# SmartHive_Client.net
KiCad netlist of a schematic drawn in Altium Designer
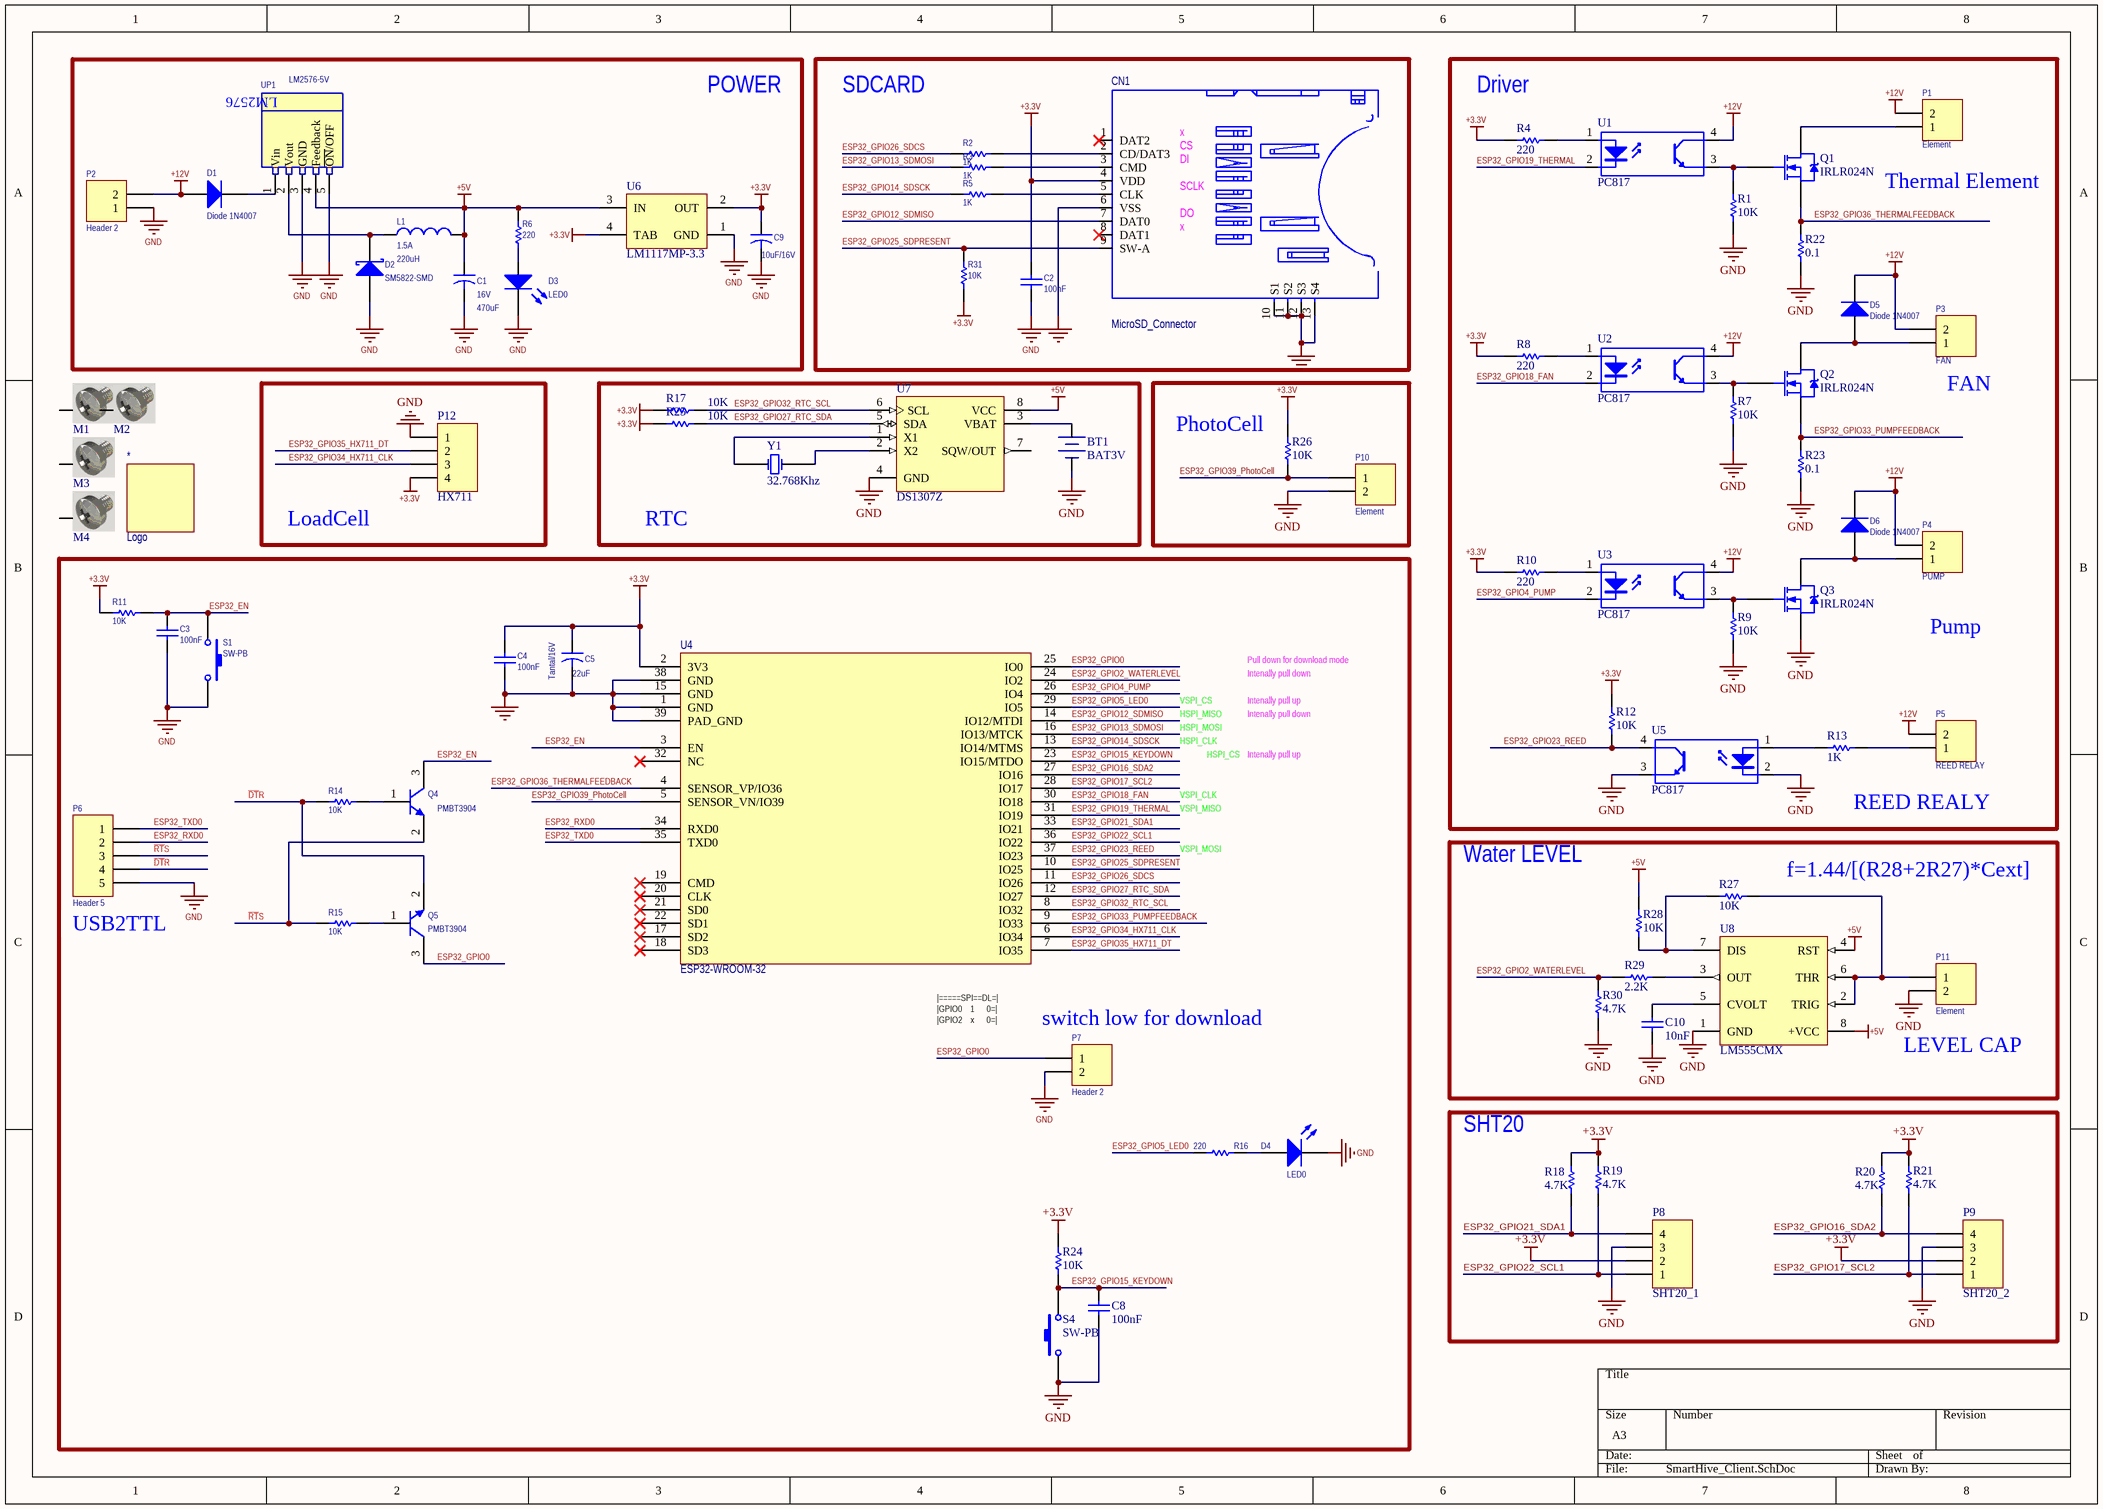
[diagram p0: SmartHive_Client.SchDoc]

(export (version "E")
  (design (tool "Eeschema 10.0.6"))
  (components
    (comp (ref "*") (value "Logo") (footprint "LOGO_PARS_TOP") (libsource (lib "Mofidi3D") (part "Logo")))
    (comp (ref "BT1")
      (value "BAT3V")
      (footprint "BTH2032_DIP")
      (description "Battry Backup")
      (fields (field (name "DESIGNER") "Abbas Basereh"))
      (libsource (lib "Mofidi3D") (part "Battry Backup"))
    )
    (comp (ref "C1")
      (value "16V")
      (footprint "Cap electrolitic radial 8x12-3.5")
      (description "Capacitor")
      (fields (field (name "ALTIUM_VALUE") "470uF") (field (name "PUBLISHER") "Altium Limited"))
      (libsource (lib "Miscellaneous Devices") (part "Cap2"))
    )
    (comp (ref "C2")
      (value "100nF")
      (footprint "CAP0805")
      (description "Capacitor")
      (fields (field (name "PUBLISHER") "Altium Limited"))
      (libsource (lib "Miscellaneous Devices") (part "Cap"))
    )
    (comp (ref "C3")
      (value "100nF")
      (footprint "CAP0805")
      (description "Capacitor")
      (fields (field (name "PUBLISHER") "Altium Limited"))
      (libsource (lib "Miscellaneous Devices") (part "Cap"))
    )
    (comp (ref "C4")
      (value "100nF")
      (footprint "CAP0805")
      (description "Capacitor")
      (fields (field (name "PUBLISHER") "Altium Limited"))
      (libsource (lib "Miscellaneous Devices") (part "Cap"))
    )
    (comp (ref "C5")
      (value "Tantal/16V")
      (footprint "CAP_TANTAL_TYPE_B")
      (description "Capacitor")
      (fields (field (name "ALTIUM_VALUE") "22uF") (field (name "PUBLISHER") "Altium Limited"))
      (libsource (lib "Miscellaneous Devices") (part "Cap2"))
    )
    (comp (ref "C8")
      (value "100nF")
      (footprint "CAP0805")
      (description "Capacitor")
      (fields (field (name "PUBLISHER") "Altium Limited"))
      (libsource (lib "Miscellaneous Devices") (part "Cap"))
    )
    (comp (ref "C9")
      (value "10uF/16V")
      (footprint "Cap electrolitic radial 5x11-2")
      (description "Capacitor")
      (fields (field (name "PUBLISHER") "Altium Limited"))
      (libsource (lib "Miscellaneous Devices") (part "Cap2"))
    )
    (comp (ref "C10")
      (value "10nF")
      (footprint "CAP0805")
      (description "Capacitor")
      (fields (field (name "PUBLISHER") "Altium Limited"))
      (libsource (lib "Miscellaneous Devices") (part "Cap"))
    )
    (comp (ref "CN1")
      (value "MicroSD_Connector")
      (footprint "MICRO_SD_TFP-09-2-12B")
      (libsource (lib "Mofidi3D") (part "MicroSD_Connector"))
    )
    (comp (ref "D1")
      (value "Diode 1N4007")
      (footprint "DO-241AC")
      (description "1 Amp General Purpose Rectifier")
      (fields (field (name "PUBLISHER") "Altium Limited"))
      (libsource (lib "Miscellaneous Devices") (part "Diode 1N4007"))
    )
    (comp (ref "D2")
      (value "SM5822-SMD")
      (footprint "430X270D")
      (description "Schottky Diode")
      (fields (field (name "PUBLISHER") "Altium Limited"))
      (libsource (lib "Miscellaneous Devices") (part "D Schottky"))
    )
    (comp (ref "D3")
      (value "LED0")
      (footprint "LED5MM_GRN")
      (description "Typical INFRARED GaAs LED")
      (fields (field (name "PUBLISHER") "Altium Limited"))
      (libsource (lib "Miscellaneous Devices") (part "LED0"))
    )
    (comp (ref "D4")
      (value "LED0")
      (footprint "LED5MM_BLUE")
      (description "Typical INFRARED GaAs LED")
      (fields (field (name "PUBLISHER") "Altium Limited"))
      (libsource (lib "Miscellaneous Devices") (part "LED0"))
    )
    (comp (ref "D5")
      (value "Diode 1N4007")
      (footprint "DO-241AC")
      (description "1 Amp General Purpose Rectifier")
      (fields (field (name "PUBLISHER") "Altium Limited"))
      (libsource (lib "Miscellaneous Devices") (part "Diode 1N4007"))
    )
    (comp (ref "D6")
      (value "Diode 1N4007")
      (footprint "DO-241AC")
      (description "1 Amp General Purpose Rectifier")
      (fields (field (name "PUBLISHER") "Altium Limited"))
      (libsource (lib "Miscellaneous Devices") (part "Diode 1N4007"))
    )
    (comp (ref "L1")
      (value "1.5A")
      (footprint "Inductor 10x12 (200 mils)")
      (description "Inductor")
      (fields (field (name "ALTIUM_VALUE") "220uH") (field (name "PUBLISHER") "Altium Limited"))
      (libsource (lib "Miscellaneous Devices") (part "Inductor"))
    )
    (comp (ref "M1")
      (value "Screw3mm")
      (footprint "Board Screw 3mm")
      (description "Board Screw With Spacer 3mm")
      (fields (field (name "DESIGNER") "Abbas Basereh"))
      (libsource (lib "Mofidi3D") (part "Board Screw 3mm"))
    )
    (comp (ref "M2")
      (value "Screw3mm")
      (footprint "Board Screw 3mm")
      (description "Board Screw With Spacer 3mm")
      (fields (field (name "DESIGNER") "Abbas Basereh"))
      (libsource (lib "Mofidi3D") (part "Board Screw 3mm"))
    )
    (comp (ref "M3")
      (value "Screw3mm")
      (footprint "Board Screw 3mm")
      (description "Board Screw With Spacer 3mm")
      (fields (field (name "DESIGNER") "Abbas Basereh"))
      (libsource (lib "Mofidi3D") (part "Board Screw 3mm"))
    )
    (comp (ref "M4")
      (value "Screw3mm")
      (footprint "Board Screw 3mm")
      (description "Board Screw With Spacer 3mm")
      (fields (field (name "DESIGNER") "Abbas Basereh"))
      (libsource (lib "Mofidi3D") (part "Board Screw 3mm"))
    )
    (comp (ref "P1")
      (value "Element")
      (footprint "MSTBV 2,5/2-G-5")
      (description "Header, 2-Pin")
      (fields (field (name "PUBLISHER") "Altium Limited"))
      (libsource (lib "Miscellaneous Connectors") (part "Header 2"))
    )
    (comp (ref "P2")
      (value "Header 2")
      (footprint "MSTBV 2,5/2-G-5")
      (description "Header, 2-Pin")
      (fields (field (name "PUBLISHER") "Altium Limited"))
      (libsource (lib "") (part "Header 2_2"))
    )
    (comp (ref "P3")
      (value "FAN")
      (footprint "MSTBV 2,5/2-G-5")
      (description "Header, 2-Pin")
      (fields (field (name "PUBLISHER") "Altium Limited"))
      (libsource (lib "Miscellaneous Connectors") (part "Header 2"))
    )
    (comp (ref "P4")
      (value "PUMP")
      (footprint "MSTBV 2,5/2-G-5")
      (description "Header, 2-Pin")
      (fields (field (name "PUBLISHER") "Altium Limited"))
      (libsource (lib "Miscellaneous Connectors") (part "Header 2"))
    )
    (comp (ref "P5")
      (value "REED RELAY")
      (footprint "MSTBV 2,5/2-G-5")
      (description "Header, 2-Pin")
      (fields (field (name "PUBLISHER") "Altium Limited"))
      (libsource (lib "Miscellaneous Connectors") (part "Header 2"))
    )
    (comp (ref "P6")
      (value "Header 5")
      (footprint "HDR1X5")
      (description "Header, 5-Pin")
      (fields (field (name "PUBLISHER") "Altium Limited"))
      (libsource (lib "Miscellaneous Connectors") (part "Header 5"))
    )
    (comp (ref "P7")
      (value "Header 2")
      (footprint "Jumper Small - 2.54 - Black")
      (description "Header, 2-Pin")
      (fields (field (name "PUBLISHER") "Altium Limited"))
      (libsource (lib "") (part "Header 2_1"))
    )
    (comp (ref "P8")
      (value "SHT20_1")
      (footprint "XH-4PIN")
      (description "Header, 4-Pin")
      (fields (field (name "PUBLISHER") "Altium Limited"))
      (libsource (lib "Miscellaneous Connectors") (part "Header 4"))
    )
    (comp (ref "P9")
      (value "SHT20_2")
      (footprint "XH-4PIN")
      (description "Header, 4-Pin")
      (fields (field (name "PUBLISHER") "Altium Limited"))
      (libsource (lib "Miscellaneous Connectors") (part "Header 4"))
    )
    (comp (ref "P10")
      (value "Element")
      (footprint "DS1070-2-COMCON")
      (description "Header, 2-Pin")
      (fields (field (name "PUBLISHER") "Altium Limited"))
      (libsource (lib "") (part "Header 2_1"))
    )
    (comp (ref "P11")
      (value "Element")
      (footprint "DS1070-2-COMCON")
      (description "Header, 2-Pin")
      (fields (field (name "PUBLISHER") "Altium Limited"))
      (libsource (lib "") (part "Header 2_1"))
    )
    (comp (ref "P12")
      (value "HX711")
      (footprint "HDR1X4")
      (description "Header, 4-Pin")
      (fields (field (name "PUBLISHER") "Altium Limited"))
      (libsource (lib "") (part "Header 4_1"))
    )
    (comp (ref "Q1")
      (value "IRLR024N")
      (footprint "TO252-3M")
      (description "HEXFET Power MOSFET")
      (fields (field (name "PUBLISHER") "Altium Limited"))
      (libsource (lib "IR Discrete MOSFET - Power") (part "IRLR024N"))
    )
    (comp (ref "Q2")
      (value "IRLR024N")
      (footprint "TO252-3M")
      (description "HEXFET Power MOSFET")
      (fields (field (name "PUBLISHER") "Altium Limited"))
      (libsource (lib "IR Discrete MOSFET - Power") (part "IRLR024N"))
    )
    (comp (ref "Q3")
      (value "IRLR024N")
      (footprint "TO252-3M")
      (description "HEXFET Power MOSFET")
      (fields (field (name "PUBLISHER") "Altium Limited"))
      (libsource (lib "IR Discrete MOSFET - Power") (part "IRLR024N"))
    )
    (comp (ref "Q4")
      (value "PMBT3904")
      (footprint "Mofidi3D:SOT23_M")
      (description "NPN Switching Transistor")
      (fields (field (name "PUBLISHER") "Altium Limited"))
      (libsource (lib "Philips Discrete BJT - Low Power") (part "PMBT3904"))
    )
    (comp (ref "Q5")
      (value "PMBT3904")
      (footprint "Mofidi3D:SOT23_M")
      (description "NPN Switching Transistor")
      (fields (field (name "PUBLISHER") "Altium Limited"))
      (libsource (lib "Philips Discrete BJT - Low Power") (part "PMBT3904"))
    )
    (comp (ref "R1")
      (value "10K")
      (footprint "RES0805")
      (description "Resistor")
      (fields (field (name "PUBLISHER") "Altium Limited"))
      (libsource (lib "Miscellaneous Devices") (part "Res1"))
    )
    (comp (ref "R2")
      (value "1K")
      (footprint "RES0805")
      (description "Resistor")
      (fields (field (name "PUBLISHER") "Altium Limited"))
      (libsource (lib "Miscellaneous Devices") (part "Res1"))
    )
    (comp (ref "R3")
      (value "1K")
      (footprint "RES0805")
      (description "Resistor")
      (fields (field (name "PUBLISHER") "Altium Limited"))
      (libsource (lib "Miscellaneous Devices") (part "Res1"))
    )
    (comp (ref "R4")
      (value "220")
      (footprint "RES0805")
      (description "Resistor")
      (fields (field (name "PUBLISHER") "Altium Limited"))
      (libsource (lib "Miscellaneous Devices") (part "Res1"))
    )
    (comp (ref "R5")
      (value "1K")
      (footprint "RES0805")
      (description "Resistor")
      (fields (field (name "PUBLISHER") "Altium Limited"))
      (libsource (lib "Miscellaneous Devices") (part "Res1"))
    )
    (comp (ref "R6")
      (value "220")
      (footprint "RES0805")
      (description "Resistor")
      (fields (field (name "PUBLISHER") "Altium Limited"))
      (libsource (lib "Miscellaneous Devices") (part "Res1"))
    )
    (comp (ref "R7")
      (value "10K")
      (footprint "RES0805")
      (description "Resistor")
      (fields (field (name "PUBLISHER") "Altium Limited"))
      (libsource (lib "Miscellaneous Devices") (part "Res1"))
    )
    (comp (ref "R8")
      (value "220")
      (footprint "RES0805")
      (description "Resistor")
      (fields (field (name "PUBLISHER") "Altium Limited"))
      (libsource (lib "Miscellaneous Devices") (part "Res1"))
    )
    (comp (ref "R9")
      (value "10K")
      (footprint "RES0805")
      (description "Resistor")
      (fields (field (name "PUBLISHER") "Altium Limited"))
      (libsource (lib "Miscellaneous Devices") (part "Res1"))
    )
    (comp (ref "R10")
      (value "220")
      (footprint "RES0805")
      (description "Resistor")
      (fields (field (name "PUBLISHER") "Altium Limited"))
      (libsource (lib "Miscellaneous Devices") (part "Res1"))
    )
    (comp (ref "R11")
      (value "10K")
      (footprint "RES0805")
      (description "Resistor")
      (fields (field (name "PUBLISHER") "Altium Limited"))
      (libsource (lib "Miscellaneous Devices") (part "Res1"))
    )
    (comp (ref "R12")
      (value "10K")
      (footprint "RES0805")
      (description "Resistor")
      (fields (field (name "PUBLISHER") "Altium Limited"))
      (libsource (lib "Miscellaneous Devices") (part "Res1"))
    )
    (comp (ref "R13")
      (value "1K")
      (footprint "RES0805")
      (description "Resistor")
      (fields (field (name "PUBLISHER") "Altium Limited"))
      (libsource (lib "Miscellaneous Devices") (part "Res1"))
    )
    (comp (ref "R14")
      (value "10K")
      (footprint "RES0805")
      (description "Resistor")
      (fields (field (name "PUBLISHER") "Altium Limited"))
      (libsource (lib "Miscellaneous Devices") (part "Res1"))
    )
    (comp (ref "R15")
      (value "10K")
      (footprint "RES0805")
      (description "Resistor")
      (fields (field (name "PUBLISHER") "Altium Limited"))
      (libsource (lib "Miscellaneous Devices") (part "Res1"))
    )
    (comp (ref "R16")
      (value "220")
      (footprint "RES0805")
      (description "Resistor")
      (fields (field (name "PUBLISHER") "Altium Limited"))
      (libsource (lib "Miscellaneous Devices") (part "Res1"))
    )
    (comp (ref "R17")
      (value "10K")
      (footprint "RES0805")
      (description "Resistor")
      (fields (field (name "PUBLISHER") "Altium Limited"))
      (libsource (lib "Miscellaneous Devices") (part "Res1"))
    )
    (comp (ref "R18")
      (value "4.7K")
      (footprint "RES0805")
      (description "Resistor")
      (fields (field (name "PUBLISHER") "Altium Limited"))
      (libsource (lib "Miscellaneous Devices") (part "Res1"))
    )
    (comp (ref "R19")
      (value "4.7K")
      (footprint "RES0805")
      (description "Resistor")
      (fields (field (name "PUBLISHER") "Altium Limited"))
      (libsource (lib "Miscellaneous Devices") (part "Res1"))
    )
    (comp (ref "R20")
      (value "4.7K")
      (footprint "RES0805")
      (description "Resistor")
      (fields (field (name "PUBLISHER") "Altium Limited"))
      (libsource (lib "Miscellaneous Devices") (part "Res1"))
    )
    (comp (ref "R21")
      (value "4.7K")
      (footprint "RES0805")
      (description "Resistor")
      (fields (field (name "PUBLISHER") "Altium Limited"))
      (libsource (lib "Miscellaneous Devices") (part "Res1"))
    )
    (comp (ref "R22")
      (value "0.1")
      (footprint "RES2512")
      (description "Size:2512,1%")
      (fields (field (name "PUBLISHER") "Altium Limited"))
      (libsource (lib "Miscellaneous Devices") (part "Res1"))
    )
    (comp (ref "R23")
      (value "0.1")
      (footprint "RES2512")
      (description "Size:2512,1%")
      (fields (field (name "PUBLISHER") "Altium Limited"))
      (libsource (lib "Miscellaneous Devices") (part "Res1"))
    )
    (comp (ref "R24")
      (value "10K")
      (footprint "RES0805")
      (description "Resistor")
      (fields (field (name "PUBLISHER") "Altium Limited"))
      (libsource (lib "Miscellaneous Devices") (part "Res1"))
    )
    (comp (ref "R25")
      (value "10K")
      (footprint "RES0805")
      (description "Resistor")
      (fields (field (name "PUBLISHER") "Altium Limited"))
      (libsource (lib "Miscellaneous Devices") (part "Res1"))
    )
    (comp (ref "R26")
      (value "10K")
      (footprint "RES0805")
      (description "Resistor")
      (fields (field (name "PUBLISHER") "Altium Limited"))
      (libsource (lib "Miscellaneous Devices") (part "Res1"))
    )
    (comp (ref "R27")
      (value "10K")
      (footprint "RES0805")
      (description "Resistor")
      (fields (field (name "PUBLISHER") "Altium Limited"))
      (libsource (lib "Miscellaneous Devices") (part "Res1"))
    )
    (comp (ref "R28")
      (value "10K")
      (footprint "RES0805")
      (description "Resistor")
      (fields (field (name "PUBLISHER") "Altium Limited"))
      (libsource (lib "Miscellaneous Devices") (part "Res1"))
    )
    (comp (ref "R29")
      (value "2.2K")
      (footprint "RES0805")
      (description "Resistor")
      (fields (field (name "PUBLISHER") "Altium Limited"))
      (libsource (lib "Miscellaneous Devices") (part "Res1"))
    )
    (comp (ref "R30")
      (value "4.7K")
      (footprint "RES0805")
      (description "Resistor")
      (fields (field (name "PUBLISHER") "Altium Limited"))
      (libsource (lib "Miscellaneous Devices") (part "Res1"))
    )
    (comp (ref "R31")
      (value "10K")
      (footprint "RES0805")
      (description "Resistor")
      (fields (field (name "PUBLISHER") "Altium Limited"))
      (libsource (lib "Miscellaneous Devices") (part "Res1"))
    )
    (comp (ref "S1")
      (value "SW-PB")
      (footprint "SW-2PIN-SMD")
      (description "Switch")
      (fields (field (name "PUBLISHER") "Altium Limited"))
      (libsource (lib "Miscellaneous Devices") (part "SW-PB"))
    )
    (comp (ref "S4")
      (value "SW-PB")
      (footprint "SW-4PIN")
      (description "Switch")
      (fields (field (name "PUBLISHER") "Altium Limited"))
      (libsource (lib "Miscellaneous Devices") (part "SW-PB"))
    )
    (comp (ref "U1")
      (value "PC817")
      (footprint "DIP_4")
      (description "4-Pin Phototransistor Optocoupler")
      (fields (field (name "PUBLISHER") "Altium Limited"))
      (libsource (lib "Miscellaneous Devices") (part "Optoisolator1"))
    )
    (comp (ref "U2")
      (value "PC817")
      (footprint "DIP_4")
      (description "4-Pin Phototransistor Optocoupler")
      (fields (field (name "PUBLISHER") "Altium Limited"))
      (libsource (lib "Miscellaneous Devices") (part "Optoisolator1"))
    )
    (comp (ref "U3")
      (value "PC817")
      (footprint "DIP_4")
      (description "4-Pin Phototransistor Optocoupler")
      (fields (field (name "PUBLISHER") "Altium Limited"))
      (libsource (lib "Miscellaneous Devices") (part "Optoisolator1"))
    )
    (comp (ref "U4")
      (value "ESP32-WROOM-32")
      (footprint "ESP32-WROOM-32D")
      (description "ESP32  a single chip 2.4 GHz Wi-Fi and Bluetooth combo chip")
      (libsource (lib "Mofidi3D") (part "ESP32-WROOM-32"))
    )
    (comp (ref "U5")
      (value "PC817")
      (footprint "DIP_4")
      (description "4-Pin Phototransistor Optocoupler")
      (fields (field (name "PUBLISHER") "Altium Limited"))
      (libsource (lib "Miscellaneous Devices") (part "Optoisolator1"))
    )
    (comp (ref "U6")
      (value "LM1117MP-3.3")
      (footprint "SOT223_4")
      (description "800mA Low-Dropout Linear Regulator, 4-pin SOT-223")
      (fields
        (field (name "MANUFACTURER") "National Semiconductor")
        (field (name "PUBLISHER") "Altium Limited")
      )
      (libsource (lib "NSC LDO") (part "LM1117MP-3.3"))
    )
    (comp (ref "U7")
      (value "DS1307Z")
      (footprint "SO-8N")
      (description "64 X 8 Serial Real-Time Clock")
      (fields (field (name "PUBLISHER") "Altium Limited"))
      (libsource (lib "Dallas Peripheral Real Time Clock") (part "DS1307Z"))
    )
    (comp (ref "U8")
      (value "LM555CMX")
      (footprint "SO-8N")
      (description "Timer, 8-pin Narrow SOIC")
      (fields
        (field (name "MANUFACTURER") "National Semiconductor")
        (field (name "PUBLISHER") "Altium Limited")
      )
      (libsource (lib "NSC Analog") (part "LM555CMX"))
    )
    (comp (ref "UP1")
      (value "LM2576-5V")
      (footprint "TO-220_5 with heatsink HS sot32")
      (description "3.3V, 3A variable output step-down switching voltage regulator")
      (fields (field (name "DESIGNER") "Abbas Basereh"))
      (libsource (lib "Mofidi3D") (part "LM2576-Adj"))
    )
    (comp (ref "Y1")
      (value "32.768Khz")
      (footprint "Crystal_NC308")
      (description "XTAL Crystal")
      (fields (field (name "DESIGNER") "ABBAS BASEREH"))
      (libsource (lib "Mofidi3D") (part "XTAL_Crystal"))
    )
  )
  (nets
    (net (code "1") (name "+3.3V") (class "Default")
      (node (ref "C2") (pin "2") (pinfunction "2_2") (pintype "passive"))
      (node (ref "C4") (pin "2") (pinfunction "2_2") (pintype "passive"))
      (node (ref "C5") (pin "1") (pinfunction "1_1") (pintype "passive"))
      (node (ref "C9") (pin "1") (pinfunction "1_1") (pintype "passive"))
      (node (ref "CN1") (pin "4") (pinfunction "VDD_4") (pintype "passive"))
      (node (ref "P12") (pin "4") (pinfunction "4_4") (pintype "passive"))
      (node (ref "P8") (pin "2") (pinfunction "2_2") (pintype "passive"))
      (node (ref "P9") (pin "2") (pinfunction "2_2") (pintype "passive"))
      (node (ref "R10") (pin "1") (pinfunction "1_1") (pintype "passive"))
      (node (ref "R11") (pin "2") (pinfunction "2_2") (pintype "passive"))
      (node (ref "R12") (pin "2") (pinfunction "2_2") (pintype "passive"))
      (node (ref "R17") (pin "2") (pinfunction "2_2") (pintype "passive"))
      (node (ref "R18") (pin "2") (pinfunction "2_2") (pintype "passive"))
      (node (ref "R19") (pin "2") (pinfunction "2_2") (pintype "passive"))
      (node (ref "R20") (pin "2") (pinfunction "2_2") (pintype "passive"))
      (node (ref "R21") (pin "2") (pinfunction "2_2") (pintype "passive"))
      (node (ref "R24") (pin "2") (pinfunction "2_2") (pintype "passive"))
      (node (ref "R25") (pin "2") (pinfunction "2_2") (pintype "passive"))
      (node (ref "R26") (pin "2") (pinfunction "2_2") (pintype "passive"))
      (node (ref "R31") (pin "2") (pinfunction "2_2") (pintype "passive"))
      (node (ref "R4") (pin "1") (pinfunction "1_1") (pintype "passive"))
      (node (ref "R8") (pin "1") (pinfunction "1_1") (pintype "passive"))
      (node (ref "U4") (pin "2") (pinfunction "3V3_2") (pintype "power_in"))
      (node (ref "U6") (pin "2") (pinfunction "OUT_2") (pintype "power_in"))
      (node (ref "U6") (pin "4") (pinfunction "TAB_4") (pintype "power_in"))
    )
    (net (code "2") (name "+5V") (class "Default")
      (node (ref "C1") (pin "1") (pinfunction "1_1") (pintype "passive"))
      (node (ref "L1") (pin "2") (pinfunction "2_2") (pintype "passive"))
      (node (ref "R28") (pin "2") (pinfunction "2_2") (pintype "passive"))
      (node (ref "R6") (pin "2") (pinfunction "2_2") (pintype "passive"))
      (node (ref "U6") (pin "3") (pinfunction "IN_3") (pintype "power_in"))
      (node (ref "U7") (pin "8") (pinfunction "VCC_8") (pintype "power_in"))
      (node (ref "U8") (pin "4") (pinfunction "RST_4") (pintype "input"))
      (node (ref "U8") (pin "8") (pinfunction "+VCC_8") (pintype "power_in"))
      (node (ref "UP1") (pin "4") (pinfunction "Feedback_4") (pintype "passive"))
    )
    (net (code "3") (name "+12V") (class "Default")
      (node (ref "D1") (pin "1") (pinfunction "A_1") (pintype "passive"))
      (node (ref "D5") (pin "2") (pinfunction "K_2") (pintype "passive"))
      (node (ref "D6") (pin "2") (pinfunction "K_2") (pintype "passive"))
      (node (ref "P1") (pin "2") (pinfunction "2_2") (pintype "passive"))
      (node (ref "P2") (pin "2") (pinfunction "2_2") (pintype "passive"))
      (node (ref "P3") (pin "2") (pinfunction "2_2") (pintype "passive"))
      (node (ref "P4") (pin "2") (pinfunction "2_2") (pintype "passive"))
      (node (ref "P5") (pin "2") (pinfunction "2_2") (pintype "passive"))
      (node (ref "U1") (pin "4") (pinfunction "C_4") (pintype "passive"))
      (node (ref "U2") (pin "4") (pinfunction "C_4") (pintype "passive"))
      (node (ref "U3") (pin "4") (pinfunction "C_4") (pintype "passive"))
    )
    (net (code "4") (name "/ESP32_EN") (class "Default")
      (node (ref "C3") (pin "2") (pinfunction "2_2") (pintype "passive"))
      (node (ref "Q4") (pin "3") (pinfunction "C_3") (pintype "passive"))
      (node (ref "R11") (pin "1") (pinfunction "1_1") (pintype "passive"))
      (node (ref "S1") (pin "1") (pinfunction "1_1") (pintype "passive"))
      (node (ref "U4") (pin "3") (pinfunction "EN_3") (pintype "passive"))
    )
    (net (code "5") (name "/ESP32_GPIO0") (class "Default")
      (node (ref "P7") (pin "1") (pinfunction "1_1") (pintype "passive"))
      (node (ref "Q5") (pin "3") (pinfunction "C_3") (pintype "passive"))
      (node (ref "U4") (pin "25") (pinfunction "IO0_25") (pintype "passive"))
    )
    (net (code "6") (name "/ESP32_GPIO2_WATERLEVEL") (class "Default")
      (node (ref "R29") (pin "2") (pinfunction "2_2") (pintype "passive"))
      (node (ref "R30") (pin "2") (pinfunction "2_2") (pintype "passive"))
      (node (ref "U4") (pin "24") (pinfunction "IO2_24") (pintype "passive"))
    )
    (net (code "7") (name "/ESP32_GPIO4_PUMP") (class "Default")
      (node (ref "U3") (pin "2") (pinfunction "K_2") (pintype "passive"))
      (node (ref "U4") (pin "26") (pinfunction "IO4_26") (pintype "passive"))
    )
    (net (code "8") (name "/ESP32_GPIO5_LED0") (class "Default")
      (node (ref "R16") (pin "1") (pinfunction "1_1") (pintype "passive"))
      (node (ref "U4") (pin "29") (pinfunction "IO5_29") (pintype "passive"))
    )
    (net (code "9") (name "/ESP32_GPIO12_SDMISO") (class "Default")
      (node (ref "CN1") (pin "7") (pinfunction "DAT0_7") (pintype "passive"))
      (node (ref "U4") (pin "14") (pinfunction "IO12/MTDI_14") (pintype "passive"))
    )
    (net (code "10") (name "/ESP32_GPIO13_SDMOSI") (class "Default")
      (node (ref "R3") (pin "2") (pinfunction "2_2") (pintype "passive"))
      (node (ref "U4") (pin "16") (pinfunction "IO13/MTCK_16") (pintype "passive"))
    )
    (net (code "11") (name "/ESP32_GPIO14_SDSCK") (class "Default")
      (node (ref "R5") (pin "2") (pinfunction "2_2") (pintype "passive"))
      (node (ref "U4") (pin "13") (pinfunction "IO14/MTMS_13") (pintype "passive"))
    )
    (net (code "12") (name "/ESP32_GPIO15_KEYDOWN") (class "Default")
      (node (ref "C8") (pin "2") (pinfunction "2_2") (pintype "passive"))
      (node (ref "R24") (pin "1") (pinfunction "1_1") (pintype "passive"))
      (node (ref "S4") (pin "1") (pinfunction "1_1") (pintype "passive"))
      (node (ref "U4") (pin "23") (pinfunction "IO15/MTDO_23") (pintype "passive"))
    )
    (net (code "13") (name "/ESP32_GPIO16_SDA2") (class "Default")
      (node (ref "P9") (pin "4") (pinfunction "4_4") (pintype "passive"))
      (node (ref "R20") (pin "1") (pinfunction "1_1") (pintype "passive"))
      (node (ref "U4") (pin "27") (pinfunction "IO16_27") (pintype "passive"))
    )
    (net (code "14") (name "/ESP32_GPIO17_SCL2") (class "Default")
      (node (ref "P9") (pin "1") (pinfunction "1_1") (pintype "passive"))
      (node (ref "R21") (pin "1") (pinfunction "1_1") (pintype "passive"))
      (node (ref "U4") (pin "28") (pinfunction "IO17_28") (pintype "passive"))
    )
    (net (code "15") (name "/ESP32_GPIO18_FAN") (class "Default")
      (node (ref "U2") (pin "2") (pinfunction "K_2") (pintype "passive"))
      (node (ref "U4") (pin "30") (pinfunction "IO18_30") (pintype "passive"))
    )
    (net (code "16") (name "/ESP32_GPIO19_THERMAL") (class "Default")
      (node (ref "U1") (pin "2") (pinfunction "K_2") (pintype "passive"))
      (node (ref "U4") (pin "31") (pinfunction "IO19_31") (pintype "passive"))
    )
    (net (code "17") (name "/ESP32_GPIO21_SDA1") (class "Default")
      (node (ref "P8") (pin "4") (pinfunction "4_4") (pintype "passive"))
      (node (ref "R18") (pin "1") (pinfunction "1_1") (pintype "passive"))
      (node (ref "U4") (pin "33") (pinfunction "IO21_33") (pintype "passive"))
    )
    (net (code "18") (name "/ESP32_GPIO22_SCL1") (class "Default")
      (node (ref "P8") (pin "1") (pinfunction "1_1") (pintype "passive"))
      (node (ref "R19") (pin "1") (pinfunction "1_1") (pintype "passive"))
      (node (ref "U4") (pin "36") (pinfunction "IO22_36") (pintype "passive"))
    )
    (net (code "19") (name "/ESP32_GPIO23_REED") (class "Default")
      (node (ref "R12") (pin "1") (pinfunction "1_1") (pintype "passive"))
      (node (ref "U4") (pin "37") (pinfunction "IO23_37") (pintype "passive"))
      (node (ref "U5") (pin "4") (pinfunction "C_4") (pintype "passive"))
    )
    (net (code "20") (name "/ESP32_GPIO25_SDPRESENT") (class "Default")
      (node (ref "CN1") (pin "9") (pinfunction "SW-A_9") (pintype "passive"))
      (node (ref "R31") (pin "1") (pinfunction "1_1") (pintype "passive"))
      (node (ref "U4") (pin "10") (pinfunction "IO25_10") (pintype "passive"))
    )
    (net (code "21") (name "/ESP32_GPIO26_SDCS") (class "Default")
      (node (ref "R2") (pin "2") (pinfunction "2_2") (pintype "passive"))
      (node (ref "U4") (pin "11") (pinfunction "IO26_11") (pintype "passive"))
    )
    (net (code "22") (name "/ESP32_GPIO27_RTC_SDA") (class "Default")
      (node (ref "R25") (pin "1") (pinfunction "1_1") (pintype "passive"))
      (node (ref "U4") (pin "12") (pinfunction "IO27_12") (pintype "passive"))
      (node (ref "U7") (pin "5") (pinfunction "SDA_5") (pintype "bidirectional"))
    )
    (net (code "23") (name "/ESP32_GPIO32_RTC_SCL") (class "Default")
      (node (ref "R17") (pin "1") (pinfunction "1_1") (pintype "passive"))
      (node (ref "U4") (pin "8") (pinfunction "IO32_8") (pintype "passive"))
      (node (ref "U7") (pin "6") (pinfunction "SCL_6") (pintype "input"))
    )
    (net (code "24") (name "/ESP32_GPIO33_PUMPFEEDBACK") (class "Default")
      (node (ref "Q2") (pin "3") (pinfunction "S_3") (pintype "passive"))
      (node (ref "R23") (pin "2") (pinfunction "2_2") (pintype "passive"))
      (node (ref "U4") (pin "9") (pinfunction "IO33_9") (pintype "passive"))
    )
    (net (code "25") (name "/ESP32_GPIO34_HX711_CLK") (class "Default")
      (node (ref "P12") (pin "3") (pinfunction "3_3") (pintype "passive"))
      (node (ref "U4") (pin "6") (pinfunction "IO34_6") (pintype "passive"))
    )
    (net (code "26") (name "/ESP32_GPIO35_HX711_DT") (class "Default")
      (node (ref "P12") (pin "2") (pinfunction "2_2") (pintype "passive"))
      (node (ref "U4") (pin "7") (pinfunction "IO35_7") (pintype "passive"))
    )
    (net (code "27") (name "/ESP32_GPIO36_THERMALFEEDBACK") (class "Default")
      (node (ref "Q1") (pin "3") (pinfunction "S_3") (pintype "passive"))
      (node (ref "R22") (pin "2") (pinfunction "2_2") (pintype "passive"))
      (node (ref "U4") (pin "4") (pinfunction "SENSOR_VP/IO36_4") (pintype "passive"))
    )
    (net (code "28") (name "/ESP32_GPIO39_PhotoCell") (class "Default")
      (node (ref "P10") (pin "1") (pinfunction "1_1") (pintype "passive"))
      (node (ref "R26") (pin "1") (pinfunction "1_1") (pintype "passive"))
      (node (ref "U4") (pin "5") (pinfunction "SENSOR_VN/IO39_5") (pintype "passive"))
    )
    (net (code "29") (name "/ESP32_RXD0") (class "Default")
      (node (ref "P6") (pin "2") (pinfunction "2_2") (pintype "passive"))
      (node (ref "U4") (pin "34") (pinfunction "RXD0_34") (pintype "passive"))
    )
    (net (code "30") (name "/ESP32_TXD0") (class "Default")
      (node (ref "P6") (pin "1") (pinfunction "1_1") (pintype "passive"))
      (node (ref "U4") (pin "35") (pinfunction "TXD0_35") (pintype "passive"))
    )
    (net (code "31") (name "/~{DT}R") (class "Default")
      (node (ref "P6") (pin "4") (pinfunction "4_4") (pintype "passive"))
      (node (ref "Q5") (pin "2") (pinfunction "E_2") (pintype "passive"))
      (node (ref "R14") (pin "2") (pinfunction "2_2") (pintype "passive"))
    )
    (net (code "32") (name "/~{RT}S") (class "Default")
      (node (ref "P6") (pin "3") (pinfunction "3_3") (pintype "passive"))
      (node (ref "Q4") (pin "2") (pinfunction "E_2") (pintype "passive"))
      (node (ref "R15") (pin "2") (pinfunction "2_2") (pintype "passive"))
    )
    (net (code "33") (name "GND") (class "Default")
      (node (ref "BT1") (pin "2") (pinfunction "-_2") (pintype "passive"))
      (node (ref "C1") (pin "2") (pinfunction "2_2") (pintype "passive"))
      (node (ref "C10") (pin "1") (pinfunction "1_1") (pintype "passive"))
      (node (ref "C2") (pin "1") (pinfunction "1_1") (pintype "passive"))
      (node (ref "C3") (pin "1") (pinfunction "1_1") (pintype "passive"))
      (node (ref "C4") (pin "1") (pinfunction "1_1") (pintype "passive"))
      (node (ref "C5") (pin "2") (pinfunction "2_2") (pintype "passive"))
      (node (ref "C8") (pin "1") (pinfunction "1_1") (pintype "passive"))
      (node (ref "C9") (pin "2") (pinfunction "2_2") (pintype "passive"))
      (node (ref "CN1") (pin "10") (pinfunction "S1_10") (pintype "passive"))
      (node (ref "CN1") (pin "11") (pinfunction "S2_11") (pintype "passive"))
      (node (ref "CN1") (pin "12") (pinfunction "S3_12") (pintype "passive"))
      (node (ref "CN1") (pin "13") (pinfunction "S4_13") (pintype "passive"))
      (node (ref "CN1") (pin "6") (pinfunction "VSS_6") (pintype "passive"))
      (node (ref "D2") (pin "1") (pinfunction "A_1") (pintype "passive"))
      (node (ref "D3") (pin "2") (pinfunction "K_2") (pintype "passive"))
      (node (ref "D4") (pin "2") (pinfunction "K_2") (pintype "passive"))
      (node (ref "P10") (pin "2") (pinfunction "2_2") (pintype "passive"))
      (node (ref "P11") (pin "2") (pinfunction "2_2") (pintype "passive"))
      (node (ref "P12") (pin "1") (pinfunction "1_1") (pintype "passive"))
      (node (ref "P2") (pin "1") (pinfunction "1_1") (pintype "passive"))
      (node (ref "P6") (pin "5") (pinfunction "5_5") (pintype "passive"))
      (node (ref "P7") (pin "2") (pinfunction "2_2") (pintype "passive"))
      (node (ref "P8") (pin "3") (pinfunction "3_3") (pintype "passive"))
      (node (ref "P9") (pin "3") (pinfunction "3_3") (pintype "passive"))
      (node (ref "Q3") (pin "3") (pinfunction "S_3") (pintype "passive"))
      (node (ref "R1") (pin "1") (pinfunction "1_1") (pintype "passive"))
      (node (ref "R22") (pin "1") (pinfunction "1_1") (pintype "passive"))
      (node (ref "R23") (pin "1") (pinfunction "1_1") (pintype "passive"))
      (node (ref "R30") (pin "1") (pinfunction "1_1") (pintype "passive"))
      (node (ref "R7") (pin "1") (pinfunction "1_1") (pintype "passive"))
      (node (ref "R9") (pin "1") (pinfunction "1_1") (pintype "passive"))
      (node (ref "S1") (pin "2") (pinfunction "2_2") (pintype "passive"))
      (node (ref "S4") (pin "2") (pinfunction "2_2") (pintype "passive"))
      (node (ref "U4") (pin "1") (pinfunction "GND_1") (pintype "power_in"))
      (node (ref "U4") (pin "15") (pinfunction "GND_15") (pintype "power_in"))
      (node (ref "U4") (pin "38") (pinfunction "GND_38") (pintype "power_in"))
      (node (ref "U4") (pin "39") (pinfunction "PAD_GND_39") (pintype "passive"))
      (node (ref "U5") (pin "2") (pinfunction "K_2") (pintype "passive"))
      (node (ref "U5") (pin "3") (pinfunction "E_3") (pintype "passive"))
      (node (ref "U6") (pin "1") (pinfunction "GND_1") (pintype "power_in"))
      (node (ref "U7") (pin "4") (pinfunction "GND_4") (pintype "power_in"))
      (node (ref "U8") (pin "1") (pinfunction "GND_1") (pintype "power_in"))
      (node (ref "UP1") (pin "3") (pinfunction "GND_3") (pintype "passive"))
      (node (ref "UP1") (pin "5") (pinfunction "~{ON}/OFF_5") (pintype "passive"))
    )
    (net (code "34") (name "Net-(BT1-+)") (class "Default")
      (node (ref "BT1") (pin "1") (pinfunction "+_1") (pintype "passive"))
      (node (ref "U7") (pin "3") (pinfunction "VBAT_3") (pintype "power_in"))
    )
    (net (code "35") (name "Net-(CN1-CD{slash}DAT3)") (class "Default")
      (node (ref "CN1") (pin "2") (pinfunction "CD/DAT3_2") (pintype "passive"))
      (node (ref "R2") (pin "1") (pinfunction "1_1") (pintype "passive"))
    )
    (net (code "36") (name "Net-(CN1-CLK)") (class "Default")
      (node (ref "CN1") (pin "5") (pinfunction "CLK_5") (pintype "passive"))
      (node (ref "R5") (pin "1") (pinfunction "1_1") (pintype "passive"))
    )
    (net (code "37") (name "Net-(CN1-CMD)") (class "Default")
      (node (ref "CN1") (pin "3") (pinfunction "CMD_3") (pintype "passive"))
      (node (ref "R3") (pin "1") (pinfunction "1_1") (pintype "passive"))
    )
    (net (code "38") (name "Net-(D1-K)") (class "Default")
      (node (ref "D1") (pin "2") (pinfunction "K_2") (pintype "passive"))
      (node (ref "UP1") (pin "1") (pinfunction "Vin_1") (pintype "passive"))
    )
    (net (code "39") (name "Net-(D2-K)") (class "Default")
      (node (ref "D2") (pin "2") (pinfunction "K_2") (pintype "passive"))
      (node (ref "L1") (pin "1") (pinfunction "1_1") (pintype "passive"))
      (node (ref "UP1") (pin "2") (pinfunction "Vout_2") (pintype "passive"))
    )
    (net (code "40") (name "Net-(D3-A)") (class "Default")
      (node (ref "D3") (pin "1") (pinfunction "A_1") (pintype "passive"))
      (node (ref "R6") (pin "1") (pinfunction "1_1") (pintype "passive"))
    )
    (net (code "41") (name "Net-(D4-A)") (class "Default")
      (node (ref "D4") (pin "1") (pinfunction "A_1") (pintype "passive"))
      (node (ref "R16") (pin "2") (pinfunction "2_2") (pintype "passive"))
    )
    (net (code "42") (name "Net-(D5-A)") (class "Default")
      (node (ref "D5") (pin "1") (pinfunction "A_1") (pintype "passive"))
      (node (ref "P3") (pin "1") (pinfunction "1_1") (pintype "passive"))
      (node (ref "Q2") (pin "4") (pinfunction "D_4") (pintype "passive"))
    )
    (net (code "43") (name "Net-(D6-A)") (class "Default")
      (node (ref "D6") (pin "1") (pinfunction "A_1") (pintype "passive"))
      (node (ref "P4") (pin "1") (pinfunction "1_1") (pintype "passive"))
      (node (ref "Q3") (pin "4") (pinfunction "D_4") (pintype "passive"))
    )
    (net (code "44") (name "Net-(P5-Pad1)") (class "Default")
      (node (ref "P5") (pin "1") (pinfunction "1_1") (pintype "passive"))
      (node (ref "R13") (pin "2") (pinfunction "2_2") (pintype "passive"))
    )
    (net (code "45") (name "Net-(Q1-D)") (class "Default")
      (node (ref "P1") (pin "1") (pinfunction "1_1") (pintype "passive"))
      (node (ref "Q1") (pin "4") (pinfunction "D_4") (pintype "passive"))
    )
    (net (code "46") (name "Net-(Q1-G)") (class "Default")
      (node (ref "Q1") (pin "1") (pinfunction "G_1") (pintype "passive"))
      (node (ref "R1") (pin "2") (pinfunction "2_2") (pintype "passive"))
      (node (ref "U1") (pin "3") (pinfunction "E_3") (pintype "passive"))
    )
    (net (code "47") (name "Net-(Q2-G)") (class "Default")
      (node (ref "Q2") (pin "1") (pinfunction "G_1") (pintype "passive"))
      (node (ref "R7") (pin "2") (pinfunction "2_2") (pintype "passive"))
      (node (ref "U2") (pin "3") (pinfunction "E_3") (pintype "passive"))
    )
    (net (code "48") (name "Net-(Q3-G)") (class "Default")
      (node (ref "Q3") (pin "1") (pinfunction "G_1") (pintype "passive"))
      (node (ref "R9") (pin "2") (pinfunction "2_2") (pintype "passive"))
      (node (ref "U3") (pin "3") (pinfunction "E_3") (pintype "passive"))
    )
    (net (code "49") (name "Net-(Q4-B)") (class "Default")
      (node (ref "Q4") (pin "1") (pinfunction "B_1") (pintype "passive"))
      (node (ref "R14") (pin "1") (pinfunction "1_1") (pintype "passive"))
    )
    (net (code "50") (name "Net-(Q5-B)") (class "Default")
      (node (ref "Q5") (pin "1") (pinfunction "B_1") (pintype "passive"))
      (node (ref "R15") (pin "1") (pinfunction "1_1") (pintype "passive"))
    )
    (net (code "51") (name "Net-(U1-A)") (class "Default")
      (node (ref "R4") (pin "2") (pinfunction "2_2") (pintype "passive"))
      (node (ref "U1") (pin "1") (pinfunction "A_1") (pintype "passive"))
    )
    (net (code "52") (name "Net-(U2-A)") (class "Default")
      (node (ref "R8") (pin "2") (pinfunction "2_2") (pintype "passive"))
      (node (ref "U2") (pin "1") (pinfunction "A_1") (pintype "passive"))
    )
    (net (code "53") (name "Net-(U3-A)") (class "Default")
      (node (ref "R10") (pin "2") (pinfunction "2_2") (pintype "passive"))
      (node (ref "U3") (pin "1") (pinfunction "A_1") (pintype "passive"))
    )
    (net (code "54") (name "Net-(U5-A)") (class "Default")
      (node (ref "R13") (pin "1") (pinfunction "1_1") (pintype "passive"))
      (node (ref "U5") (pin "1") (pinfunction "A_1") (pintype "passive"))
    )
    (net (code "55") (name "Net-(U7-X1)") (class "Default")
      (node (ref "U7") (pin "1") (pinfunction "X1_1") (pintype "input"))
      (node (ref "Y1") (pin "1") (pinfunction "OSC1_1") (pintype "passive"))
    )
    (net (code "56") (name "Net-(U7-X2)") (class "Default")
      (node (ref "U7") (pin "2") (pinfunction "X2_2") (pintype "input"))
      (node (ref "Y1") (pin "2") (pinfunction "OSC2_2") (pintype "passive"))
    )
    (net (code "57") (name "Net-(U8-CVOLT)") (class "Default")
      (node (ref "C10") (pin "2") (pinfunction "2_2") (pintype "passive"))
      (node (ref "U8") (pin "5") (pinfunction "CVOLT_5") (pintype "passive"))
    )
    (net (code "58") (name "Net-(U8-DIS)") (class "Default")
      (node (ref "R27") (pin "2") (pinfunction "2_2") (pintype "passive"))
      (node (ref "R28") (pin "1") (pinfunction "1_1") (pintype "passive"))
      (node (ref "U8") (pin "7") (pinfunction "DIS_7") (pintype "open_collector"))
    )
    (net (code "59") (name "Net-(U8-OUT)") (class "Default")
      (node (ref "R29") (pin "1") (pinfunction "1_1") (pintype "passive"))
      (node (ref "U8") (pin "3") (pinfunction "OUT_3") (pintype "output"))
    )
    (net (code "60") (name "Net-(U8-THR)") (class "Default")
      (node (ref "P11") (pin "1") (pinfunction "1_1") (pintype "passive"))
      (node (ref "R27") (pin "1") (pinfunction "1_1") (pintype "passive"))
      (node (ref "U8") (pin "2") (pinfunction "TRIG_2") (pintype "input"))
      (node (ref "U8") (pin "6") (pinfunction "THR_6") (pintype "input"))
    )
    (net (code "61") (name "unconnected-(CN1-DAT1-Pad8)") (class "Default")
      (node (ref "CN1") (pin "8") (pinfunction "DAT1_8") (pintype "passive+no_connect"))
    )
    (net (code "62") (name "unconnected-(CN1-DAT2-Pad1)") (class "Default")
      (node (ref "CN1") (pin "1") (pinfunction "DAT2_1") (pintype "passive+no_connect"))
    )
    (net (code "63") (name "unconnected-(M1-PadS)") (class "Default")
      (node (ref "M1") (pin "S") (pinfunction "S_S") (pintype "passive"))
    )
    (net (code "64") (name "unconnected-(M2-PadS)") (class "Default")
      (node (ref "M2") (pin "S") (pinfunction "S_S") (pintype "passive"))
    )
    (net (code "65") (name "unconnected-(M3-PadS)") (class "Default")
      (node (ref "M3") (pin "S") (pinfunction "S_S") (pintype "passive"))
    )
    (net (code "66") (name "unconnected-(M4-PadS)") (class "Default")
      (node (ref "M4") (pin "S") (pinfunction "S_S") (pintype "passive"))
    )
    (net (code "67") (name "unconnected-(U4-CLK-Pad20)") (class "Default")
      (node (ref "U4") (pin "20") (pinfunction "CLK_20") (pintype "passive+no_connect"))
    )
    (net (code "68") (name "unconnected-(U4-CMD-Pad19)") (class "Default")
      (node (ref "U4") (pin "19") (pinfunction "CMD_19") (pintype "passive+no_connect"))
    )
    (net (code "69") (name "unconnected-(U4-NC-Pad32)") (class "Default")
      (node (ref "U4") (pin "32") (pinfunction "NC_32") (pintype "passive+no_connect"))
    )
    (net (code "70") (name "unconnected-(U4-SD0-Pad21)") (class "Default")
      (node (ref "U4") (pin "21") (pinfunction "SD0_21") (pintype "passive+no_connect"))
    )
    (net (code "71") (name "unconnected-(U4-SD1-Pad22)") (class "Default")
      (node (ref "U4") (pin "22") (pinfunction "SD1_22") (pintype "passive+no_connect"))
    )
    (net (code "72") (name "unconnected-(U4-SD2-Pad17)") (class "Default")
      (node (ref "U4") (pin "17") (pinfunction "SD2_17") (pintype "passive+no_connect"))
    )
    (net (code "73") (name "unconnected-(U4-SD3-Pad18)") (class "Default")
      (node (ref "U4") (pin "18") (pinfunction "SD3_18") (pintype "passive+no_connect"))
    )
    (net (code "74") (name "unconnected-(U7-SQW{slash}OUT-Pad7)") (class "Default")
      (node (ref "U7") (pin "7") (pinfunction "SQW/OUT_7") (pintype "output"))
    )
  )
)
